# hand_amptrol_ver4.net
KiCad netlist of a schematic drawn in EAGLE
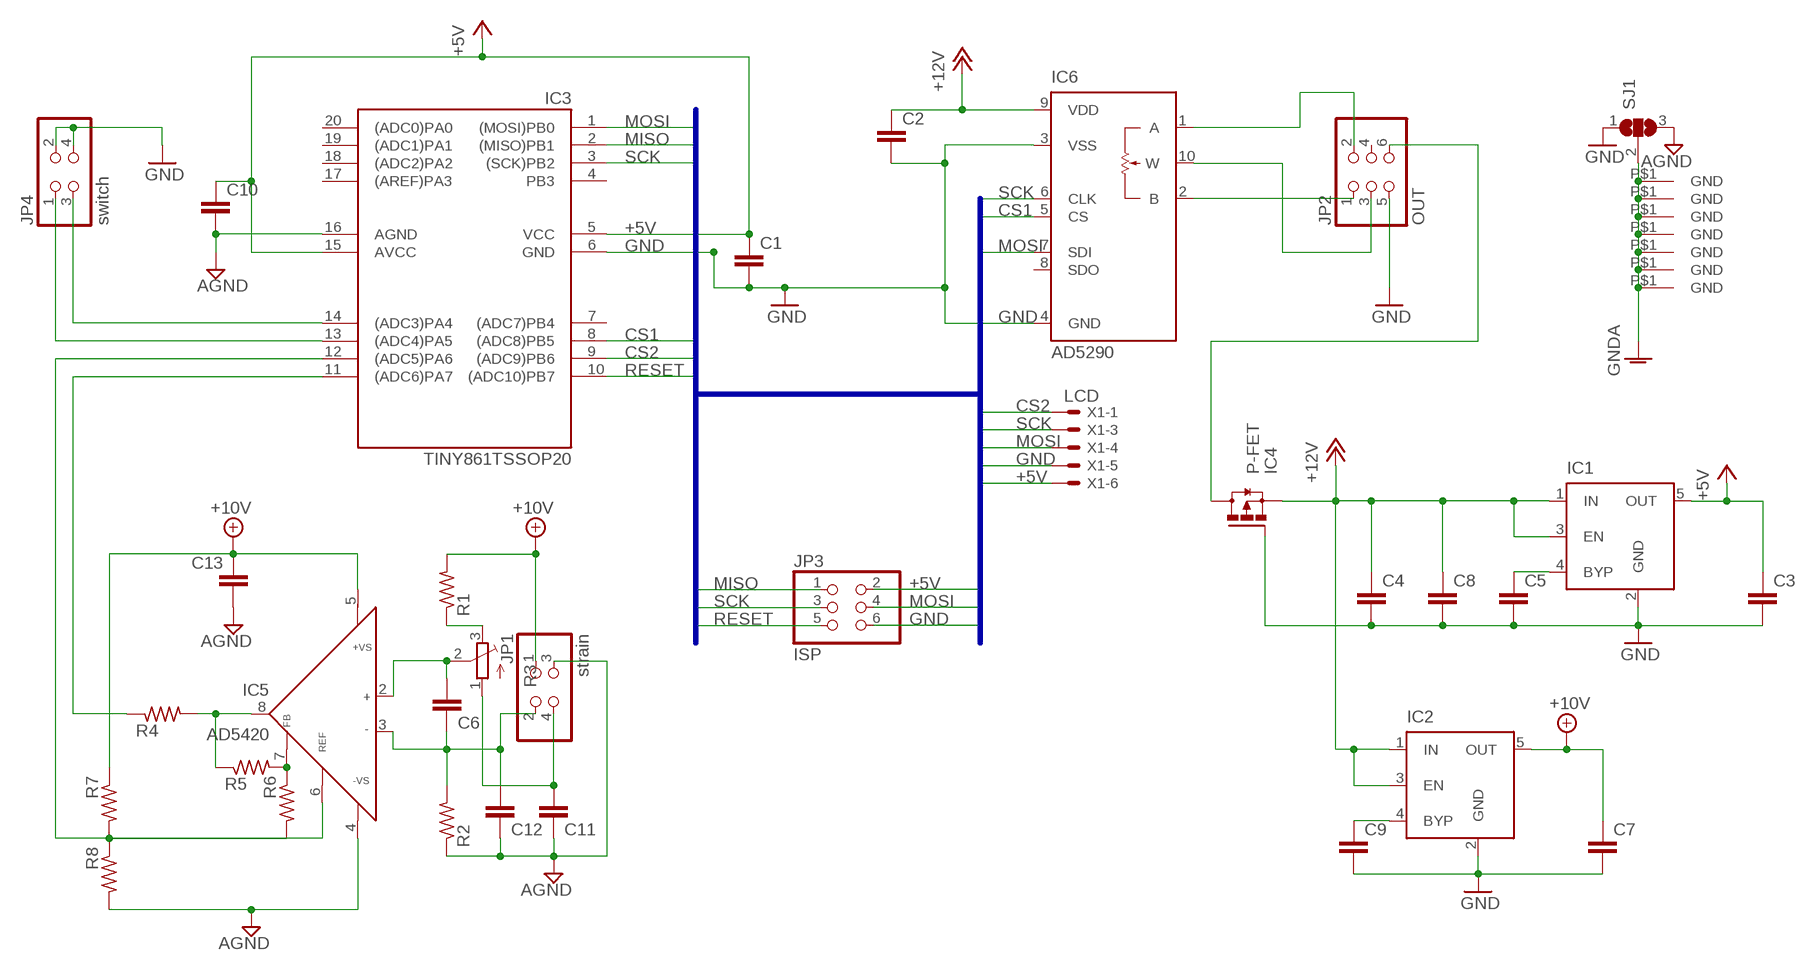
[diagram p0: schematic, sheet 1]

(export (version "E")
  (design (tool "Eeschema 10.0.6"))
  (components
    (comp (ref "C1")
      (value "C-EUC0603")
      (footprint "eagle-import:C0603")
      (libsource (lib "eagle-import") (part "C-EUC0603"))
    )
    (comp (ref "C2")
      (value "C-EUC0603")
      (footprint "eagle-import:C0603")
      (libsource (lib "eagle-import") (part "C-EUC0603"))
    )
    (comp (ref "C3")
      (value "C-EUC0603")
      (footprint "eagle-import:C0603")
      (libsource (lib "eagle-import") (part "C-EUC0603"))
    )
    (comp (ref "C4")
      (value "C-EUC1206")
      (footprint "eagle-import:C1206")
      (libsource (lib "eagle-import") (part "C-EUC1206"))
    )
    (comp (ref "C5")
      (value "C-EUC0603")
      (footprint "eagle-import:C0603")
      (libsource (lib "eagle-import") (part "C-EUC0603"))
    )
    (comp (ref "C6")
      (value "C-EUC0603")
      (footprint "eagle-import:C0603")
      (libsource (lib "eagle-import") (part "C-EUC0603"))
    )
    (comp (ref "C7")
      (value "C-EUC0603")
      (footprint "eagle-import:C0603")
      (libsource (lib "eagle-import") (part "C-EUC0603"))
    )
    (comp (ref "C8")
      (value "C-EUC0603")
      (footprint "eagle-import:C0603")
      (libsource (lib "eagle-import") (part "C-EUC0603"))
    )
    (comp (ref "C9")
      (value "C-EUC0603")
      (footprint "eagle-import:C0603")
      (libsource (lib "eagle-import") (part "C-EUC0603"))
    )
    (comp (ref "C10")
      (value "C-EUC0603")
      (footprint "eagle-import:C0603")
      (libsource (lib "eagle-import") (part "C-EUC0603"))
    )
    (comp (ref "C11")
      (value "C-EUC0603")
      (footprint "eagle-import:C0603")
      (libsource (lib "eagle-import") (part "C-EUC0603"))
    )
    (comp (ref "C12")
      (value "C-EUC0603")
      (footprint "eagle-import:C0603")
      (libsource (lib "eagle-import") (part "C-EUC0603"))
    )
    (comp (ref "C13")
      (value "C-EUC0603")
      (footprint "eagle-import:C0603")
      (libsource (lib "eagle-import") (part "C-EUC0603"))
    )
    (comp (ref "IC1")
      (value "MIC5219XX")
      (footprint "eagle-import:SOT23-5")
      (libsource (lib "eagle-import") (part "MIC5219XX"))
    )
    (comp (ref "IC2")
      (value "MIC5219XX")
      (footprint "eagle-import:SOT23-5")
      (libsource (lib "eagle-import") (part "MIC5219XX"))
    )
    (comp (ref "IC3")
      (value "TINY861TSSOP20")
      (footprint "eagle-import:TSSOP20")
      (libsource (lib "eagle-import") (part "TINY861TSSOP20"))
    )
    (comp (ref "IC4")
      (value "P-FET")
      (footprint "eagle-import:SOT23")
      (libsource (lib "eagle-import") (part "P-FET"))
    )
    (comp (ref "IC5")
      (value "AD5420")
      (footprint "eagle-import:MSOP08")
      (libsource (lib "eagle-import") (part "AD5420"))
    )
    (comp (ref "IC6")
      (value "AD5290")
      (footprint "eagle-import:MSOP10")
      (libsource (lib "eagle-import") (part "AD5290"))
    )
    (comp (ref "JP1")
      (value "strain")
      (footprint "eagle-import:2X02")
      (libsource (lib "eagle-import") (part "PINHD-2X2"))
    )
    (comp (ref "JP2")
      (value "OUT")
      (footprint "eagle-import:2X03")
      (libsource (lib "eagle-import") (part "PINHD-2X3"))
    )
    (comp (ref "JP3")
      (value "ISP")
      (footprint "eagle-import:2X03")
      (libsource (lib "eagle-import") (part "PINHD-2X3"))
    )
    (comp (ref "JP4")
      (value "switch")
      (footprint "eagle-import:2X02")
      (libsource (lib "eagle-import") (part "PINHD-2X2"))
    )
    (comp (ref "R1")
      (value "R-US_R0603")
      (footprint "eagle-import:R0603")
      (libsource (lib "eagle-import") (part "R-US_R0603"))
    )
    (comp (ref "R2")
      (value "R-US_R0603")
      (footprint "eagle-import:R0603")
      (libsource (lib "eagle-import") (part "R-US_R0603"))
    )
    (comp (ref "R3")
      (value "TRIM_EU-3223W")
      (footprint "eagle-import:3223W")
      (libsource (lib "eagle-import") (part "TRIM_EU-3223W"))
    )
    (comp (ref "R4")
      (value "R-US_R0603")
      (footprint "eagle-import:R0603")
      (libsource (lib "eagle-import") (part "R-US_R0603"))
    )
    (comp (ref "R5")
      (value "R-US_R0603")
      (footprint "eagle-import:R0603")
      (libsource (lib "eagle-import") (part "R-US_R0603"))
    )
    (comp (ref "R6")
      (value "R-US_R0603")
      (footprint "eagle-import:R0603")
      (libsource (lib "eagle-import") (part "R-US_R0603"))
    )
    (comp (ref "R7")
      (value "R-US_R0603")
      (footprint "eagle-import:R0603")
      (libsource (lib "eagle-import") (part "R-US_R0603"))
    )
    (comp (ref "R8")
      (value "R-US_R0603")
      (footprint "eagle-import:R0603")
      (libsource (lib "eagle-import") (part "R-US_R0603"))
    )
    (comp (ref "SJ1")
      (value "SJ2W")
      (footprint "eagle-import:SJ_2")
      (libsource (lib "eagle-import") (part "SJ2W"))
    )
    (comp (ref "U$5")
      (value "GRDSMALL")
      (footprint "eagle-import:GNDSMALL")
      (libsource (lib "eagle-import") (part "GRDSMALL"))
    )
    (comp (ref "U$6")
      (value "GRDSMALL")
      (footprint "eagle-import:GNDSMALL")
      (libsource (lib "eagle-import") (part "GRDSMALL"))
    )
    (comp (ref "U$7")
      (value "GRDSMALL")
      (footprint "eagle-import:GNDSMALL")
      (libsource (lib "eagle-import") (part "GRDSMALL"))
    )
    (comp (ref "U$8")
      (value "GRDSMALL")
      (footprint "eagle-import:GNDSMALL")
      (libsource (lib "eagle-import") (part "GRDSMALL"))
    )
    (comp (ref "U$9")
      (value "GRDSMALL")
      (footprint "eagle-import:GNDSMALL")
      (libsource (lib "eagle-import") (part "GRDSMALL"))
    )
    (comp (ref "U$10")
      (value "GRDSMALL")
      (footprint "eagle-import:GNDSMALL")
      (libsource (lib "eagle-import") (part "GRDSMALL"))
    )
    (comp (ref "U$11")
      (value "GRDSMALL")
      (footprint "eagle-import:GNDSMALL")
      (libsource (lib "eagle-import") (part "GRDSMALL"))
    )
    (comp (ref "X1")
      (value "LCD")
      (footprint "eagle-import:22-23-2061")
      (fields (field (name "MF") "MOLEX") (field (name "MPN") "22-23-2061"))
      (libsource (lib "eagle-import") (part "22-23-2061"))
    )
  )
  (nets
    (net (code "1") (name "+5V") (class "Default")
      (node (ref "C1") (pin "1") (pinfunction "1_1") (pintype "passive"))
      (node (ref "C10") (pin "1") (pinfunction "1_1") (pintype "passive"))
      (node (ref "C3") (pin "1") (pinfunction "1_1") (pintype "passive"))
      (node (ref "IC1") (pin "5") (pinfunction "OUT_5") (pintype "output"))
      (node (ref "IC3") (pin "15") (pinfunction "AVCC_15") (pintype "power_in"))
      (node (ref "IC3") (pin "5") (pinfunction "VCC_5") (pintype "power_in"))
      (node (ref "JP3") (pin "2") (pinfunction "2_2") (pintype "passive"))
      (node (ref "X1") (pin "6") (pinfunction "S_6") (pintype "passive"))
    )
    (net (code "2") (name "+10V") (class "Default")
      (node (ref "C13") (pin "1") (pinfunction "1_1") (pintype "passive"))
      (node (ref "C7") (pin "1") (pinfunction "1_1") (pintype "passive"))
      (node (ref "IC2") (pin "5") (pinfunction "OUT_5") (pintype "output"))
      (node (ref "IC5") (pin "5") (pinfunction "+VS_5") (pintype "input"))
      (node (ref "JP1") (pin "1") (pinfunction "1_1") (pintype "passive"))
      (node (ref "R1") (pin "2") (pinfunction "2_2") (pintype "passive"))
      (node (ref "R7") (pin "1") (pinfunction "1_1") (pintype "passive"))
    )
    (net (code "3") (name "+12V") (class "Default")
      (node (ref "C2") (pin "1") (pinfunction "1_1") (pintype "passive"))
      (node (ref "C4") (pin "1") (pinfunction "1_1") (pintype "passive"))
      (node (ref "C8") (pin "1") (pinfunction "1_1") (pintype "passive"))
      (node (ref "IC1") (pin "1") (pinfunction "IN_1") (pintype "input"))
      (node (ref "IC1") (pin "3") (pinfunction "EN_3") (pintype "input"))
      (node (ref "IC2") (pin "1") (pinfunction "IN_1") (pintype "input"))
      (node (ref "IC2") (pin "3") (pinfunction "EN_3") (pintype "input"))
      (node (ref "IC4") (pin "2") (pinfunction "S_2") (pintype "passive"))
      (node (ref "IC6") (pin "9") (pinfunction "VDD_9") (pintype "power_in"))
    )
    (net (code "4") (name "/CS1") (class "Default")
      (node (ref "IC3") (pin "8") (pinfunction "(ADC8)PB5_8") (pintype "bidirectional"))
      (node (ref "IC6") (pin "5") (pinfunction "CS_5") (pintype "input"))
    )
    (net (code "5") (name "/CS2") (class "Default")
      (node (ref "IC3") (pin "9") (pinfunction "(ADC9)PB6_9") (pintype "bidirectional"))
      (node (ref "X1") (pin "1") (pinfunction "S_1") (pintype "passive"))
    )
    (net (code "6") (name "/MISO") (class "Default")
      (node (ref "IC3") (pin "2") (pinfunction "(MISO)PB1_2") (pintype "bidirectional"))
      (node (ref "JP3") (pin "1") (pinfunction "1_1") (pintype "passive"))
    )
    (net (code "7") (name "/MOSI") (class "Default")
      (node (ref "IC3") (pin "1") (pinfunction "(MOSI)PB0_1") (pintype "bidirectional"))
      (node (ref "IC6") (pin "7") (pinfunction "SDI_7") (pintype "input"))
      (node (ref "JP3") (pin "4") (pinfunction "4_4") (pintype "passive"))
      (node (ref "X1") (pin "4") (pinfunction "S_4") (pintype "passive"))
    )
    (net (code "8") (name "/RESET") (class "Default")
      (node (ref "IC3") (pin "10") (pinfunction "(ADC10)PB7_10") (pintype "bidirectional"))
      (node (ref "JP3") (pin "5") (pinfunction "5_5") (pintype "passive"))
    )
    (net (code "9") (name "/SCK") (class "Default")
      (node (ref "IC3") (pin "3") (pinfunction "(SCK)PB2_3") (pintype "bidirectional"))
      (node (ref "IC6") (pin "6") (pinfunction "CLK_6") (pintype "bidirectional"))
      (node (ref "JP3") (pin "3") (pinfunction "3_3") (pintype "passive"))
      (node (ref "X1") (pin "3") (pinfunction "S_3") (pintype "passive"))
    )
    (net (code "10") (name "AGND") (class "Default")
      (node (ref "C10") (pin "2") (pinfunction "2_2") (pintype "passive"))
      (node (ref "C11") (pin "1") (pinfunction "1_1") (pintype "passive"))
      (node (ref "C12") (pin "1") (pinfunction "1_1") (pintype "passive"))
      (node (ref "C13") (pin "2") (pinfunction "2_2") (pintype "passive"))
      (node (ref "IC3") (pin "16") (pinfunction "AGND_16") (pintype "power_in"))
      (node (ref "IC5") (pin "4") (pinfunction "-VS_4") (pintype "input"))
      (node (ref "JP1") (pin "3") (pinfunction "3_3") (pintype "passive"))
      (node (ref "R2") (pin "1") (pinfunction "1_1") (pintype "passive"))
      (node (ref "R8") (pin "2") (pinfunction "2_2") (pintype "passive"))
      (node (ref "SJ1") (pin "3") (pinfunction "3_3") (pintype "passive"))
    )
    (net (code "11") (name "GND") (class "Default")
      (node (ref "C1") (pin "2") (pinfunction "2_2") (pintype "passive"))
      (node (ref "C2") (pin "2") (pinfunction "2_2") (pintype "passive"))
      (node (ref "C3") (pin "2") (pinfunction "2_2") (pintype "passive"))
      (node (ref "C4") (pin "2") (pinfunction "2_2") (pintype "passive"))
      (node (ref "C5") (pin "2") (pinfunction "2_2") (pintype "passive"))
      (node (ref "C7") (pin "2") (pinfunction "2_2") (pintype "passive"))
      (node (ref "C8") (pin "2") (pinfunction "2_2") (pintype "passive"))
      (node (ref "C9") (pin "2") (pinfunction "2_2") (pintype "passive"))
      (node (ref "IC1") (pin "2") (pinfunction "GND_2") (pintype "power_in"))
      (node (ref "IC2") (pin "2") (pinfunction "GND_2") (pintype "power_in"))
      (node (ref "IC3") (pin "6") (pinfunction "GND_6") (pintype "power_in"))
      (node (ref "IC4") (pin "1") (pinfunction "G_1") (pintype "passive"))
      (node (ref "IC6") (pin "3") (pinfunction "VSS_3") (pintype "power_in"))
      (node (ref "IC6") (pin "4") (pinfunction "GND_4") (pintype "power_in"))
      (node (ref "JP2") (pin "5") (pinfunction "5_5") (pintype "passive"))
      (node (ref "JP3") (pin "6") (pinfunction "6_6") (pintype "passive"))
      (node (ref "JP4") (pin "2") (pinfunction "2_2") (pintype "passive"))
      (node (ref "JP4") (pin "4") (pinfunction "4_4") (pintype "passive"))
      (node (ref "SJ1") (pin "1") (pinfunction "1_1") (pintype "passive"))
      (node (ref "X1") (pin "5") (pinfunction "S_5") (pintype "passive"))
    )
    (net (code "12") (name "GNDA") (class "Default")
      (node (ref "SJ1") (pin "2") (pinfunction "2_2") (pintype "passive"))
      (node (ref "U$10") (pin "P$1") (pinfunction "GND_P$1") (pintype "passive"))
      (node (ref "U$11") (pin "P$1") (pinfunction "GND_P$1") (pintype "passive"))
      (node (ref "U$5") (pin "P$1") (pinfunction "GND_P$1") (pintype "passive"))
      (node (ref "U$6") (pin "P$1") (pinfunction "GND_P$1") (pintype "passive"))
      (node (ref "U$7") (pin "P$1") (pinfunction "GND_P$1") (pintype "passive"))
      (node (ref "U$8") (pin "P$1") (pinfunction "GND_P$1") (pintype "passive"))
      (node (ref "U$9") (pin "P$1") (pinfunction "GND_P$1") (pintype "passive"))
    )
    (net (code "13") (name "Net-(IC1-BYP)") (class "Default")
      (node (ref "C5") (pin "1") (pinfunction "1_1") (pintype "passive"))
      (node (ref "IC1") (pin "4") (pinfunction "BYP_4") (pintype "passive"))
    )
    (net (code "14") (name "Net-(IC2-BYP)") (class "Default")
      (node (ref "C9") (pin "1") (pinfunction "1_1") (pintype "passive"))
      (node (ref "IC2") (pin "4") (pinfunction "BYP_4") (pintype "passive"))
    )
    (net (code "15") (name "Net-(IC3-(ADC3)PA4)") (class "Default")
      (node (ref "IC3") (pin "14") (pinfunction "(ADC3)PA4_14") (pintype "bidirectional"))
      (node (ref "JP4") (pin "3") (pinfunction "3_3") (pintype "passive"))
    )
    (net (code "16") (name "Net-(IC3-(ADC4)PA5)") (class "Default")
      (node (ref "IC3") (pin "13") (pinfunction "(ADC4)PA5_13") (pintype "bidirectional"))
      (node (ref "JP4") (pin "1") (pinfunction "1_1") (pintype "passive"))
    )
    (net (code "17") (name "Net-(IC3-(ADC5)PA6)") (class "Default")
      (node (ref "IC3") (pin "12") (pinfunction "(ADC5)PA6_12") (pintype "bidirectional"))
      (node (ref "IC5") (pin "6") (pinfunction "REF_6") (pintype "passive"))
      (node (ref "R6") (pin "2") (pinfunction "2_2") (pintype "passive"))
      (node (ref "R7") (pin "2") (pinfunction "2_2") (pintype "passive"))
      (node (ref "R8") (pin "1") (pinfunction "1_1") (pintype "passive"))
    )
    (net (code "18") (name "Net-(IC3-(ADC6)PA7)") (class "Default")
      (node (ref "IC3") (pin "11") (pinfunction "(ADC6)PA7_11") (pintype "bidirectional"))
      (node (ref "R4") (pin "1") (pinfunction "1_1") (pintype "passive"))
    )
    (net (code "19") (name "Net-(IC4-D)") (class "Default")
      (node (ref "IC4") (pin "3") (pinfunction "D_3") (pintype "passive"))
      (node (ref "JP2") (pin "6") (pinfunction "6_6") (pintype "passive"))
    )
    (net (code "20") (name "Net-(IC5-FB)") (class "Default")
      (node (ref "IC5") (pin "7") (pinfunction "FB_7") (pintype "passive"))
      (node (ref "R5") (pin "2") (pinfunction "2_2") (pintype "passive"))
      (node (ref "R6") (pin "1") (pinfunction "1_1") (pintype "passive"))
    )
    (net (code "21") (name "Net-(IC5-IN+)") (class "Default")
      (node (ref "C6") (pin "2") (pinfunction "2_2") (pintype "passive"))
      (node (ref "IC5") (pin "2") (pinfunction "IN+_2") (pintype "input"))
      (node (ref "R3") (pin "2") (pinfunction "S_2") (pintype "passive"))
    )
    (net (code "22") (name "Net-(IC5-IN-)") (class "Default")
      (node (ref "C12") (pin "2") (pinfunction "2_2") (pintype "passive"))
      (node (ref "C6") (pin "1") (pinfunction "1_1") (pintype "passive"))
      (node (ref "IC5") (pin "3") (pinfunction "IN-_3") (pintype "input"))
      (node (ref "JP1") (pin "2") (pinfunction "2_2") (pintype "passive"))
      (node (ref "R2") (pin "2") (pinfunction "2_2") (pintype "passive"))
    )
    (net (code "23") (name "Net-(IC5-OUT)") (class "Default")
      (node (ref "IC5") (pin "8") (pinfunction "OUT_8") (pintype "output"))
      (node (ref "R4") (pin "2") (pinfunction "2_2") (pintype "passive"))
      (node (ref "R5") (pin "1") (pinfunction "1_1") (pintype "passive"))
    )
    (net (code "24") (name "Net-(IC6-A)") (class "Default")
      (node (ref "IC6") (pin "1") (pinfunction "A_1") (pintype "passive"))
      (node (ref "JP2") (pin "2") (pinfunction "2_2") (pintype "passive"))
    )
    (net (code "25") (name "Net-(IC6-B)") (class "Default")
      (node (ref "IC6") (pin "2") (pinfunction "B_2") (pintype "passive"))
      (node (ref "JP2") (pin "1") (pinfunction "1_1") (pintype "passive"))
    )
    (net (code "26") (name "Net-(IC6-W)") (class "Default")
      (node (ref "IC6") (pin "10") (pinfunction "W_10") (pintype "passive"))
      (node (ref "JP2") (pin "3") (pinfunction "3_3") (pintype "passive"))
    )
    (net (code "27") (name "Net-(R3-A)") (class "Default")
      (node (ref "C11") (pin "2") (pinfunction "2_2") (pintype "passive"))
      (node (ref "JP1") (pin "4") (pinfunction "4_4") (pintype "passive"))
      (node (ref "R3") (pin "1") (pinfunction "A_1") (pintype "passive"))
    )
    (net (code "28") (name "Net-(R3-E)") (class "Default")
      (node (ref "R1") (pin "1") (pinfunction "1_1") (pintype "passive"))
      (node (ref "R3") (pin "3") (pinfunction "E_3") (pintype "passive"))
    )
    (net (code "29") (name "unconnected-(IC3-(ADC0)PA0-Pad20)") (class "Default")
      (node (ref "IC3") (pin "20") (pinfunction "(ADC0)PA0_20") (pintype "bidirectional"))
    )
    (net (code "30") (name "unconnected-(IC3-(ADC1)PA1-Pad19)") (class "Default")
      (node (ref "IC3") (pin "19") (pinfunction "(ADC1)PA1_19") (pintype "bidirectional"))
    )
    (net (code "31") (name "unconnected-(IC3-(ADC2)PA2-Pad18)") (class "Default")
      (node (ref "IC3") (pin "18") (pinfunction "(ADC2)PA2_18") (pintype "bidirectional"))
    )
    (net (code "32") (name "unconnected-(IC3-(ADC7)PB4-Pad7)") (class "Default")
      (node (ref "IC3") (pin "7") (pinfunction "(ADC7)PB4_7") (pintype "bidirectional"))
    )
    (net (code "33") (name "unconnected-(IC3-(AREF)PA3-Pad17)") (class "Default")
      (node (ref "IC3") (pin "17") (pinfunction "(AREF)PA3_17") (pintype "bidirectional"))
    )
    (net (code "34") (name "unconnected-(IC3-PB3-Pad4)") (class "Default")
      (node (ref "IC3") (pin "4") (pinfunction "PB3_4") (pintype "bidirectional"))
    )
    (net (code "35") (name "unconnected-(IC6-SDO-Pad8)") (class "Default")
      (node (ref "IC6") (pin "8") (pinfunction "SDO_8") (pintype "output"))
    )
    (net (code "36") (name "unconnected-(JP2-Pad4)") (class "Default")
      (node (ref "JP2") (pin "4") (pinfunction "4_4") (pintype "passive"))
    )
  )
)
